# BK1096_Power_Supply.net
KiCad netlist of a schematic drawn in Altium Designer
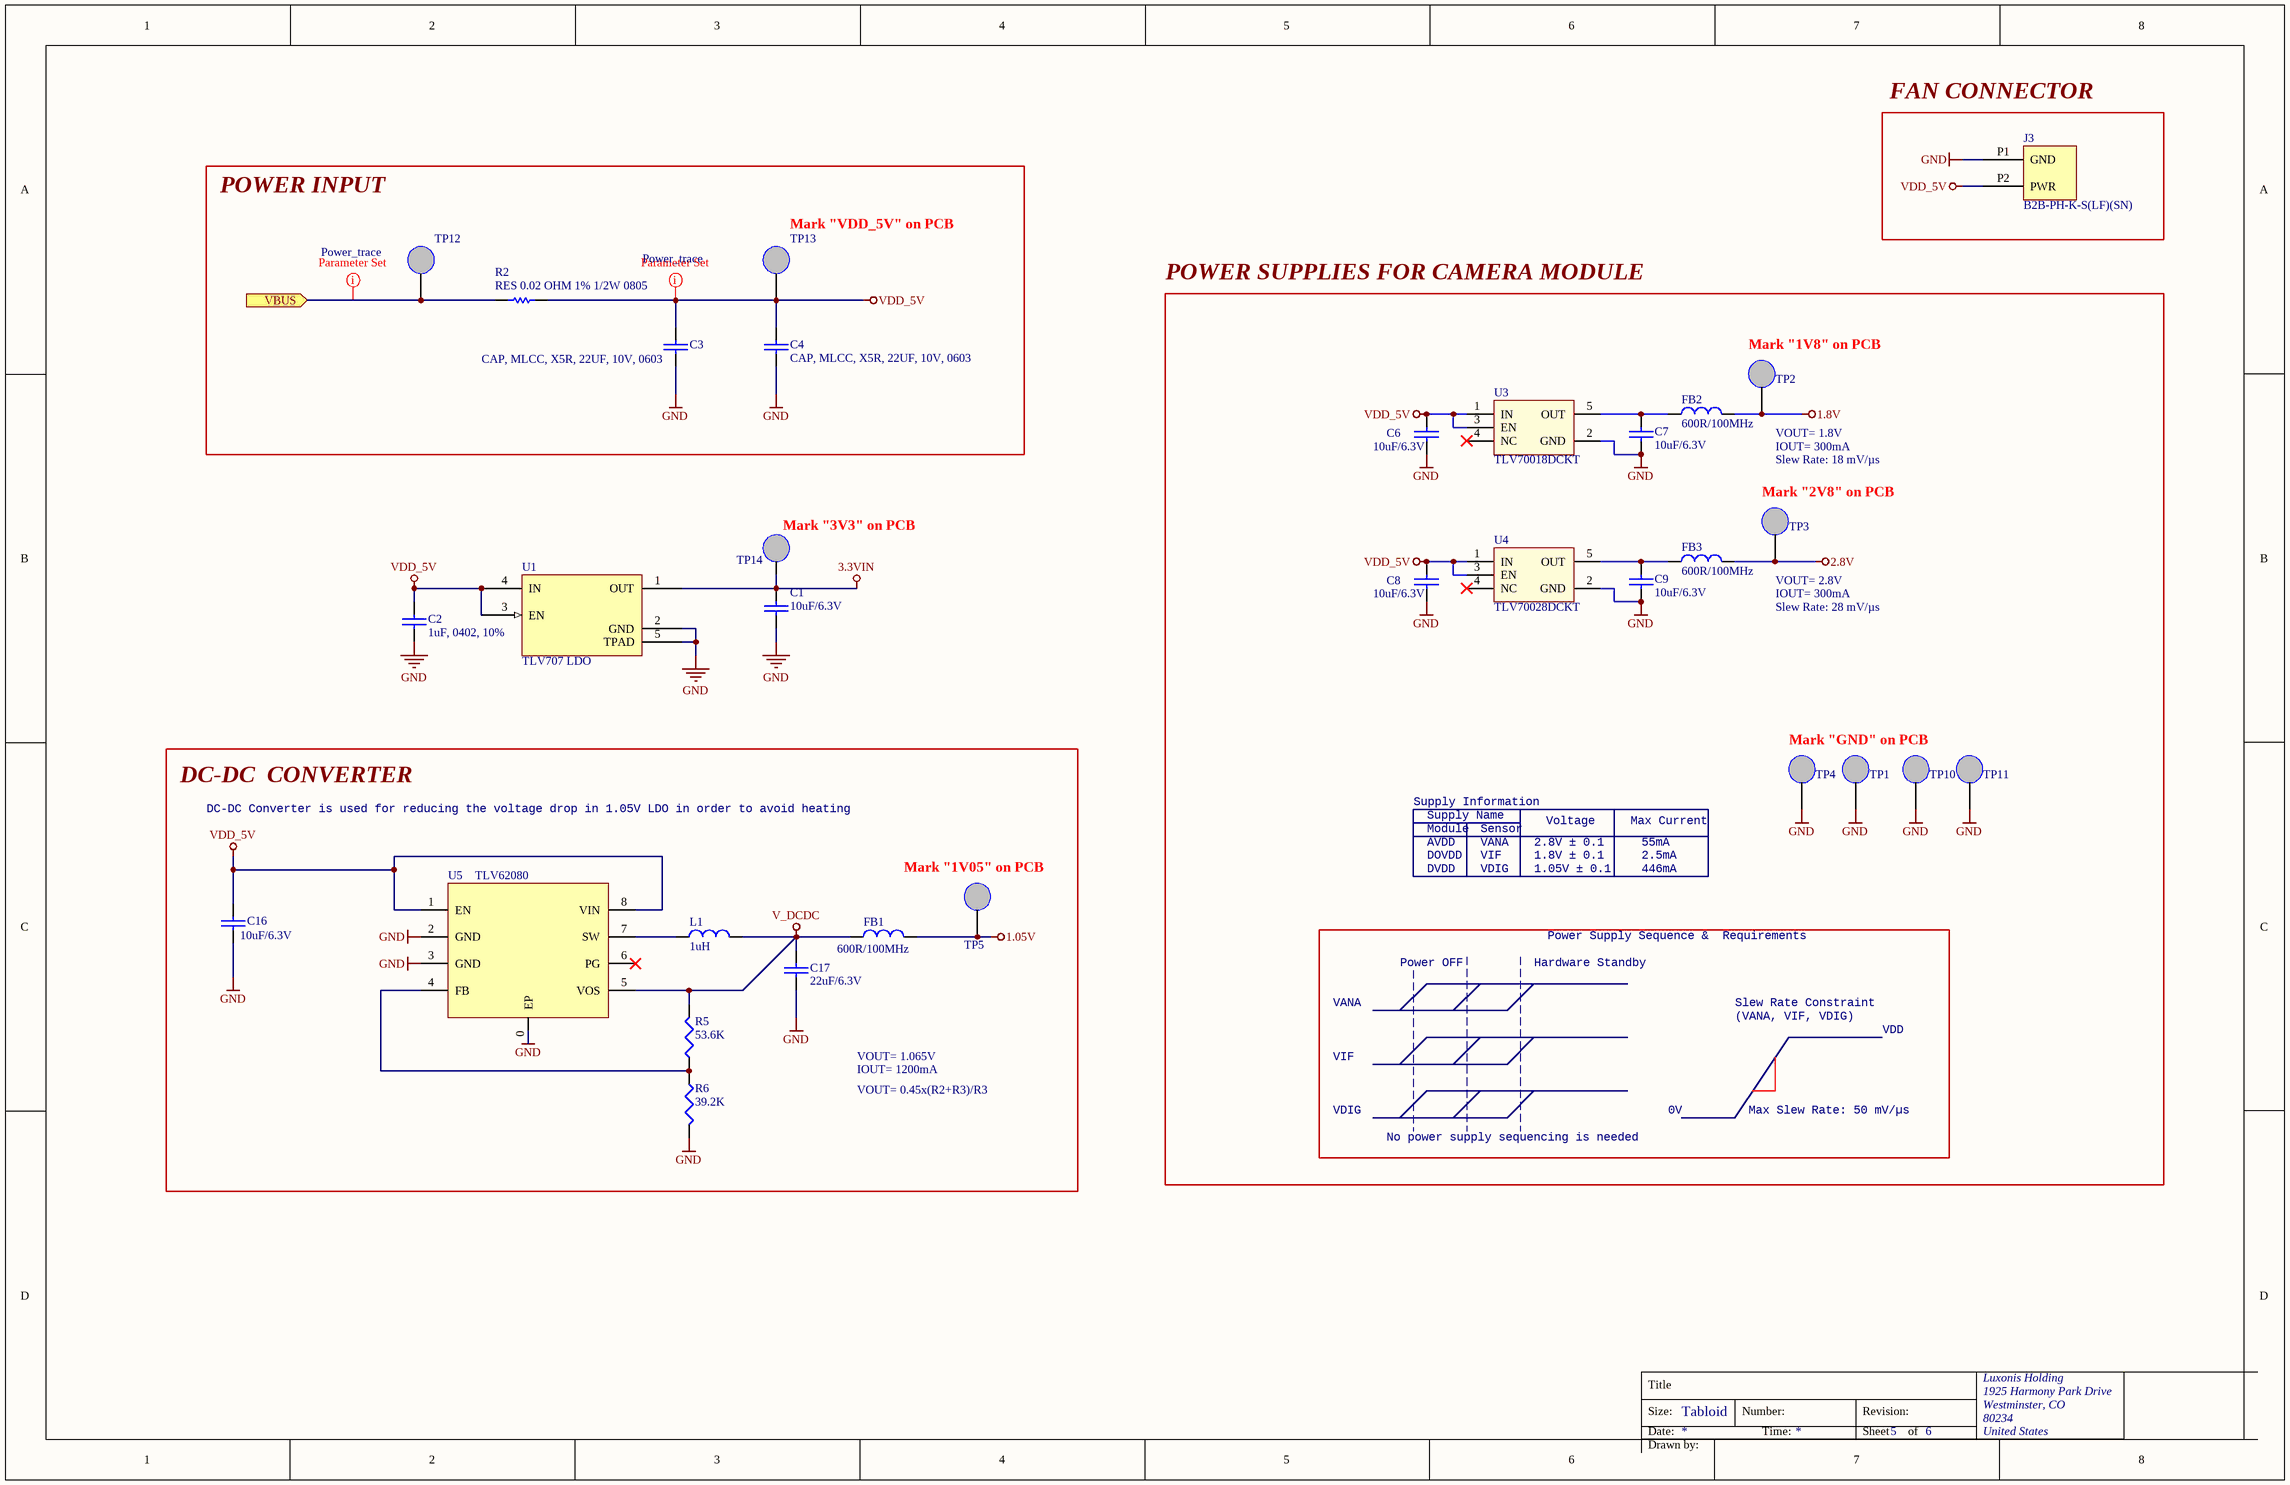
[diagram p0: BK1096_Power_Supply.SchDoc]

(export (version "E")
  (design (tool "Eeschema 10.0.6"))
  (components
    (comp (ref "C1")
      (value "10uF/6.3V")
      (footprint "IPC_RES_CAP:CAPC0402(1005)70_N")
      (description "SMD Multilayer Ceramic Capacitor, 0402 [1005 Metric], 10 µF, 6.3 V, ± 20%, X5R")
      (libsource (lib "*") (part "CAP"))
    )
    (comp (ref "C2")
      (value "1uF, 0402, 10%")
      (footprint "IPC_RES_CAP:CAPC0402(1005)70_N")
      (description "Cap Ceramic 1uF 10V X5R 10% SMD 0402 85C Paper T/R")
      (fields
        (field (name "MANUFACTURER") "Samsung")
        (field (name "MANUFACTURER PART NUMBER") "CL05A105KP5NNNC")
      )
      (libsource (lib "Schlib1") (part "CL05A105KP5NNNC"))
    )
    (comp (ref "C3")
      (value "CAP, MLCC, X5R, 22UF, 10V, 0603")
      (footprint "CAPC0603(1608)100_N")
      (libsource (lib "Schlib1") (part "GRM188R61A226ME15D"))
    )
    (comp (ref "C4")
      (value "CAP, MLCC, X5R, 22UF, 10V, 0603")
      (footprint "CAPC0603(1608)100_N")
      (libsource (lib "Schlib1") (part "GRM188R61A226ME15D"))
    )
    (comp (ref "C6")
      (value "10uF/6.3V")
      (footprint "0603")
      (description "SMD Multilayer Ceramic Capacitor, 0603 [1608 Metric], 10 µF, 6.3 V, ± 20%, X5R")
      (libsource (lib "MV0249_R0M0E0") (part "CAP"))
    )
    (comp (ref "C7")
      (value "10uF/6.3V")
      (footprint "0603")
      (description "SMD Multilayer Ceramic Capacitor, 0603 [1608 Metric], 10 µF, 6.3 V, ± 20%, X5R")
      (libsource (lib "MV0249_R0M0E0") (part "CAP"))
    )
    (comp (ref "C8")
      (value "10uF/6.3V")
      (footprint "0603")
      (description "SMD Multilayer Ceramic Capacitor, 0603 [1608 Metric], 10 µF, 6.3 V, ± 20%, X5R")
      (libsource (lib "MV0249_R0M0E0") (part "CAP"))
    )
    (comp (ref "C9")
      (value "10uF/6.3V")
      (footprint "0603")
      (description "SMD Multilayer Ceramic Capacitor, 0603 [1608 Metric], 10 µF, 6.3 V, ± 20%, X5R")
      (libsource (lib "MV0249_R0M0E0") (part "CAP"))
    )
    (comp (ref "C16")
      (value "10uF/6.3V")
      (footprint "0805")
      (description "CERAMIC CAPACITOR, 10UF, 6.3V, X5R, 20%, 0805")
      (libsource (lib "MV0249_R0M0E0") (part "CAP"))
    )
    (comp (ref "C17")
      (value "22uF/6.3V")
      (footprint "0805")
      (description "SMD Multilayer Ceramic Capacitor, 0805 [2012 Metric], 22 µF, 6.3 V, ± 10%, X5R")
      (libsource (lib "MV0249_R0M0E0") (part "CAP"))
    )
    (comp (ref "FB1")
      (value "600R/100MHz")
      (footprint "0805")
      (description "Ferrite Bead, 600 ohm, 0805 [2012 Metric], 2 A, 0.1 ohm, ± 25%")
      (libsource (lib "MV0249_R0M0E0") (part "INDUCTANCE1"))
    )
    (comp (ref "FB2")
      (value "600R/100MHz")
      (footprint "0805")
      (description "Ferrite Bead, 600 ohm, 0805 [2012 Metric], 2 A, 0.1 ohm, ± 25%")
      (libsource (lib "MV0249_R0M0E0") (part "INDUCTANCE1"))
    )
    (comp (ref "FB3")
      (value "600R/100MHz")
      (footprint "0805")
      (description "Ferrite Bead, 600 ohm, 0805 [2012 Metric], 2 A, 0.1 ohm, ± 25%")
      (libsource (lib "MV0249_R0M0E0") (part "INDUCTANCE1"))
    )
    (comp (ref "J3")
      (value "B2B-PH-K-S(LF)(SN)")
      (footprint "Luxonis:*JST_B2B-PH-K-S(LF)(SN)")
      (description "CONN HEADER VERT 2POS 2MM")
      (fields (field (name "MANUFACTURER") "JST"))
      (libsource (lib "Luxonis") (part "B2B-PH-K-S(LF)(SN)"))
    )
    (comp (ref "L1")
      (value "1uH")
      (footprint "744029001")
      (description "FIXED IND 1UH 2.2A 55 MOHM SMD")
      (libsource (lib "BK2049_FFC") (part "INDUCTANCE1_1"))
    )
    (comp (ref "R2")
      (value "RES 0.02 OHM 1% 1/2W 0805")
      (footprint "RESC0805(2012)_N")
      (libsource (lib "AltiumDesignLibrary") (part "RES"))
    )
    (comp (ref "R5")
      (value "53.6K")
      (footprint "0603")
      (description "RES SMD 53.6K OHM 1% 1/10W 0603")
      (libsource (lib "MV0249_R0M0E0") (part "RES1"))
    )
    (comp (ref "R6")
      (value "39.2K")
      (footprint "0603")
      (description "SMD Chip Resistor, Anti-Surge, 39.2 kohm, 150 V, 0603 [1608 Metric], 250 mW, ± 1%")
      (libsource (lib "MV0249_R0M0E0") (part "RES1"))
    )
    (comp (ref "TP1")
      (value "TP NM")
      (footprint "TP_SMD")
      (description "TEST POIN")
      (libsource (lib "MV0249_R0M0E0") (part "TP"))
    )
    (comp (ref "TP2")
      (value "TP NM")
      (footprint "TP_SMD")
      (description "TEST POIN")
      (libsource (lib "MV0249_R0M0E0") (part "TP"))
    )
    (comp (ref "TP3")
      (value "TP NM")
      (footprint "TP_SMD")
      (description "TEST POIN")
      (libsource (lib "MV0249_R0M0E0") (part "TP"))
    )
    (comp (ref "TP4")
      (value "TP NM")
      (footprint "TP_SMD")
      (description "TEST POIN")
      (libsource (lib "MV0249_R0M0E0") (part "TP"))
    )
    (comp (ref "TP5")
      (value "TP NM")
      (footprint "TP_SMD")
      (description "TEST POIN")
      (libsource (lib "MV0249_R0M0E0") (part "TP"))
    )
    (comp (ref "TP10")
      (value "TP NM")
      (footprint "TP_SMD")
      (description "TEST POIN")
      (libsource (lib "MV0249_R0M0E0") (part "TP"))
    )
    (comp (ref "TP11")
      (value "TP NM")
      (footprint "TP_SMD")
      (description "TEST POIN")
      (libsource (lib "MV0249_R0M0E0") (part "TP"))
    )
    (comp (ref "TP12")
      (value "TP NM")
      (footprint "TP_SMD")
      (description "TEST POIN")
      (libsource (lib "MV0249_R0M0E0") (part "TP"))
    )
    (comp (ref "TP13")
      (value "TP NM")
      (footprint "TP_SMD")
      (description "TEST POIN")
      (libsource (lib "MV0249_R0M0E0") (part "TP"))
    )
    (comp (ref "TP14")
      (value "TP NM")
      (footprint "TP_SMD")
      (description "TEST POIN")
      (libsource (lib "MV0249_R0M0E0") (part "TP"))
    )
    (comp (ref "U1")
      (value "TLV707 LDO")
      (footprint "Luxonis:DFN65P100X40-4L")
      (description "IC REG LDO 1V 0.2A 4X2SON")
      (fields
        (field (name "MANUFACTURER") "Texas Instruments")
        (field (name "MANUFACTURER PART NUMBER") "TLV70710DQNR")
      )
      (libsource (lib "Schlib1") (part "TLV707"))
    )
    (comp (ref "U3")
      (value "TLV70018DCKT")
      (footprint "SC70-5")
      (description "LDO, 200MA, 1.8V, 5SC70")
      (libsource (lib "MV0249_R0M0E0") (part "TLV70018DCKT"))
    )
    (comp (ref "U4")
      (value "TLV70028DCKT")
      (footprint "MV0235_R4M0E0:SC70-5")
      (description "LDO, 200MA, 2.8V, 5SC70")
      (libsource (lib "MV0249_R0M0E0") (part "TLV70028DCKT"))
    )
    (comp (ref "U5")
      (value "TLV62080")
      (footprint "WSON-8")
      (description "IC REG BUCK ADJ 1.2A SYNC 8WSON")
      (libsource (lib "MV0249_R0M0E0") (part "TLV62080"))
    )
  )
  (nets
    (net (code "1") (name "/VBUS") (class "Default")
      (node (ref "R2") (pin "2") (pinfunction "2_2") (pintype "passive"))
      (node (ref "TP12") (pin "1") (pinfunction "1_1") (pintype "passive"))
    )
    (net (code "2") (name "1.05V") (class "Default")
      (node (ref "FB1") (pin "2") (pinfunction "2_2") (pintype "passive"))
      (node (ref "TP5") (pin "1") (pinfunction "1_1") (pintype "passive"))
    )
    (net (code "3") (name "1.8V") (class "Default")
      (node (ref "FB2") (pin "2") (pinfunction "2_2") (pintype "passive"))
      (node (ref "TP2") (pin "1") (pinfunction "1_1") (pintype "passive"))
    )
    (net (code "4") (name "2.8V") (class "Default")
      (node (ref "FB3") (pin "2") (pinfunction "2_2") (pintype "passive"))
      (node (ref "TP3") (pin "1") (pinfunction "1_1") (pintype "passive"))
    )
    (net (code "5") (name "3.3VIN") (class "Default")
      (node (ref "C1") (pin "2") (pinfunction "2_2") (pintype "passive"))
      (node (ref "TP14") (pin "1") (pinfunction "1_1") (pintype "passive"))
      (node (ref "U1") (pin "1") (pinfunction "OUT_1") (pintype "power_in"))
    )
    (net (code "6") (name "GND") (class "Default")
      (node (ref "C1") (pin "1") (pinfunction "1_1") (pintype "passive"))
      (node (ref "C16") (pin "2") (pinfunction "2_2") (pintype "passive"))
      (node (ref "C17") (pin "2") (pinfunction "2_2") (pintype "passive"))
      (node (ref "C2") (pin "2") (pinfunction "2_2") (pintype "passive"))
      (node (ref "C3") (pin "2") (pinfunction "2_2") (pintype "passive"))
      (node (ref "C4") (pin "2") (pinfunction "2_2") (pintype "passive"))
      (node (ref "C6") (pin "2") (pinfunction "2_2") (pintype "passive"))
      (node (ref "C7") (pin "2") (pinfunction "2_2") (pintype "passive"))
      (node (ref "C8") (pin "2") (pinfunction "2_2") (pintype "passive"))
      (node (ref "C9") (pin "2") (pinfunction "2_2") (pintype "passive"))
      (node (ref "J3") (pin "P1") (pinfunction "GND_P1") (pintype "passive"))
      (node (ref "R6") (pin "2") (pintype "passive"))
      (node (ref "TP1") (pin "1") (pinfunction "1_1") (pintype "passive"))
      (node (ref "TP10") (pin "1") (pinfunction "1_1") (pintype "passive"))
      (node (ref "TP11") (pin "1") (pinfunction "1_1") (pintype "passive"))
      (node (ref "TP4") (pin "1") (pinfunction "1_1") (pintype "passive"))
      (node (ref "U1") (pin "2") (pinfunction "GND_2") (pintype "power_in"))
      (node (ref "U1") (pin "5") (pinfunction "TPAD_5") (pintype "passive"))
      (node (ref "U3") (pin "2") (pinfunction "GND_2") (pintype "passive"))
      (node (ref "U4") (pin "2") (pinfunction "GND_2") (pintype "passive"))
      (node (ref "U5") (pin "0") (pinfunction "EP_0") (pintype "passive"))
      (node (ref "U5") (pin "2") (pinfunction "GND_2") (pintype "passive"))
      (node (ref "U5") (pin "3") (pinfunction "GND_3") (pintype "passive"))
    )
    (net (code "7") (name "Net-(U3-OUT)") (class "Default")
      (node (ref "C7") (pin "1") (pinfunction "1_1") (pintype "passive"))
      (node (ref "FB2") (pin "1") (pinfunction "1_1") (pintype "passive"))
      (node (ref "U3") (pin "5") (pinfunction "OUT_5") (pintype "passive"))
    )
    (net (code "8") (name "Net-(U4-OUT)") (class "Default")
      (node (ref "C9") (pin "1") (pinfunction "1_1") (pintype "passive"))
      (node (ref "FB3") (pin "1") (pinfunction "1_1") (pintype "passive"))
      (node (ref "U4") (pin "5") (pinfunction "OUT_5") (pintype "passive"))
    )
    (net (code "9") (name "Net-(U5-FB)") (class "Default")
      (node (ref "R5") (pin "1") (pintype "passive"))
      (node (ref "R6") (pin "1") (pintype "passive"))
      (node (ref "U5") (pin "4") (pinfunction "FB_4") (pintype "passive"))
    )
    (net (code "10") (name "Net-(U5-SW)") (class "Default")
      (node (ref "L1") (pin "2") (pinfunction "2_2") (pintype "passive"))
      (node (ref "U5") (pin "7") (pinfunction "SW_7") (pintype "passive"))
    )
    (net (code "11") (name "VDD_5V") (class "Default")
      (node (ref "C16") (pin "1") (pinfunction "1_1") (pintype "passive"))
      (node (ref "C2") (pin "1") (pinfunction "1_1") (pintype "passive"))
      (node (ref "C3") (pin "1") (pinfunction "1_1") (pintype "passive"))
      (node (ref "C4") (pin "1") (pinfunction "1_1") (pintype "passive"))
      (node (ref "C6") (pin "1") (pinfunction "1_1") (pintype "passive"))
      (node (ref "C8") (pin "1") (pinfunction "1_1") (pintype "passive"))
      (node (ref "J3") (pin "P2") (pinfunction "PWR_P2") (pintype "passive"))
      (node (ref "R2") (pin "1") (pinfunction "1_1") (pintype "passive"))
      (node (ref "TP13") (pin "1") (pinfunction "1_1") (pintype "passive"))
      (node (ref "U1") (pin "3") (pinfunction "EN_3") (pintype "input"))
      (node (ref "U1") (pin "4") (pinfunction "IN_4") (pintype "power_in"))
      (node (ref "U3") (pin "1") (pinfunction "IN_1") (pintype "passive"))
      (node (ref "U3") (pin "3") (pinfunction "EN_3") (pintype "passive"))
      (node (ref "U4") (pin "1") (pinfunction "IN_1") (pintype "passive"))
      (node (ref "U4") (pin "3") (pinfunction "EN_3") (pintype "passive"))
      (node (ref "U5") (pin "1") (pinfunction "EN_1") (pintype "passive"))
      (node (ref "U5") (pin "8") (pinfunction "VIN_8") (pintype "passive"))
    )
    (net (code "12") (name "V_DCDC") (class "Default")
      (node (ref "C17") (pin "1") (pinfunction "1_1") (pintype "passive"))
      (node (ref "FB1") (pin "1") (pinfunction "1_1") (pintype "passive"))
      (node (ref "L1") (pin "1") (pinfunction "1_1") (pintype "passive"))
      (node (ref "R5") (pin "2") (pintype "passive"))
      (node (ref "U5") (pin "5") (pinfunction "VOS_5") (pintype "passive"))
    )
    (net (code "13") (name "unconnected-(U3-NC-Pad4)") (class "Default")
      (node (ref "U3") (pin "4") (pinfunction "NC_4") (pintype "passive+no_connect"))
    )
    (net (code "14") (name "unconnected-(U4-NC-Pad4)") (class "Default")
      (node (ref "U4") (pin "4") (pinfunction "NC_4") (pintype "passive+no_connect"))
    )
    (net (code "15") (name "unconnected-(U5-PG-Pad6)") (class "Default")
      (node (ref "U5") (pin "6") (pinfunction "PG_6") (pintype "passive+no_connect"))
    )
  )
)
